# MC21R01_BoardtoBoard_connectors.net
KiCad netlist of a schematic drawn in Altium Designer
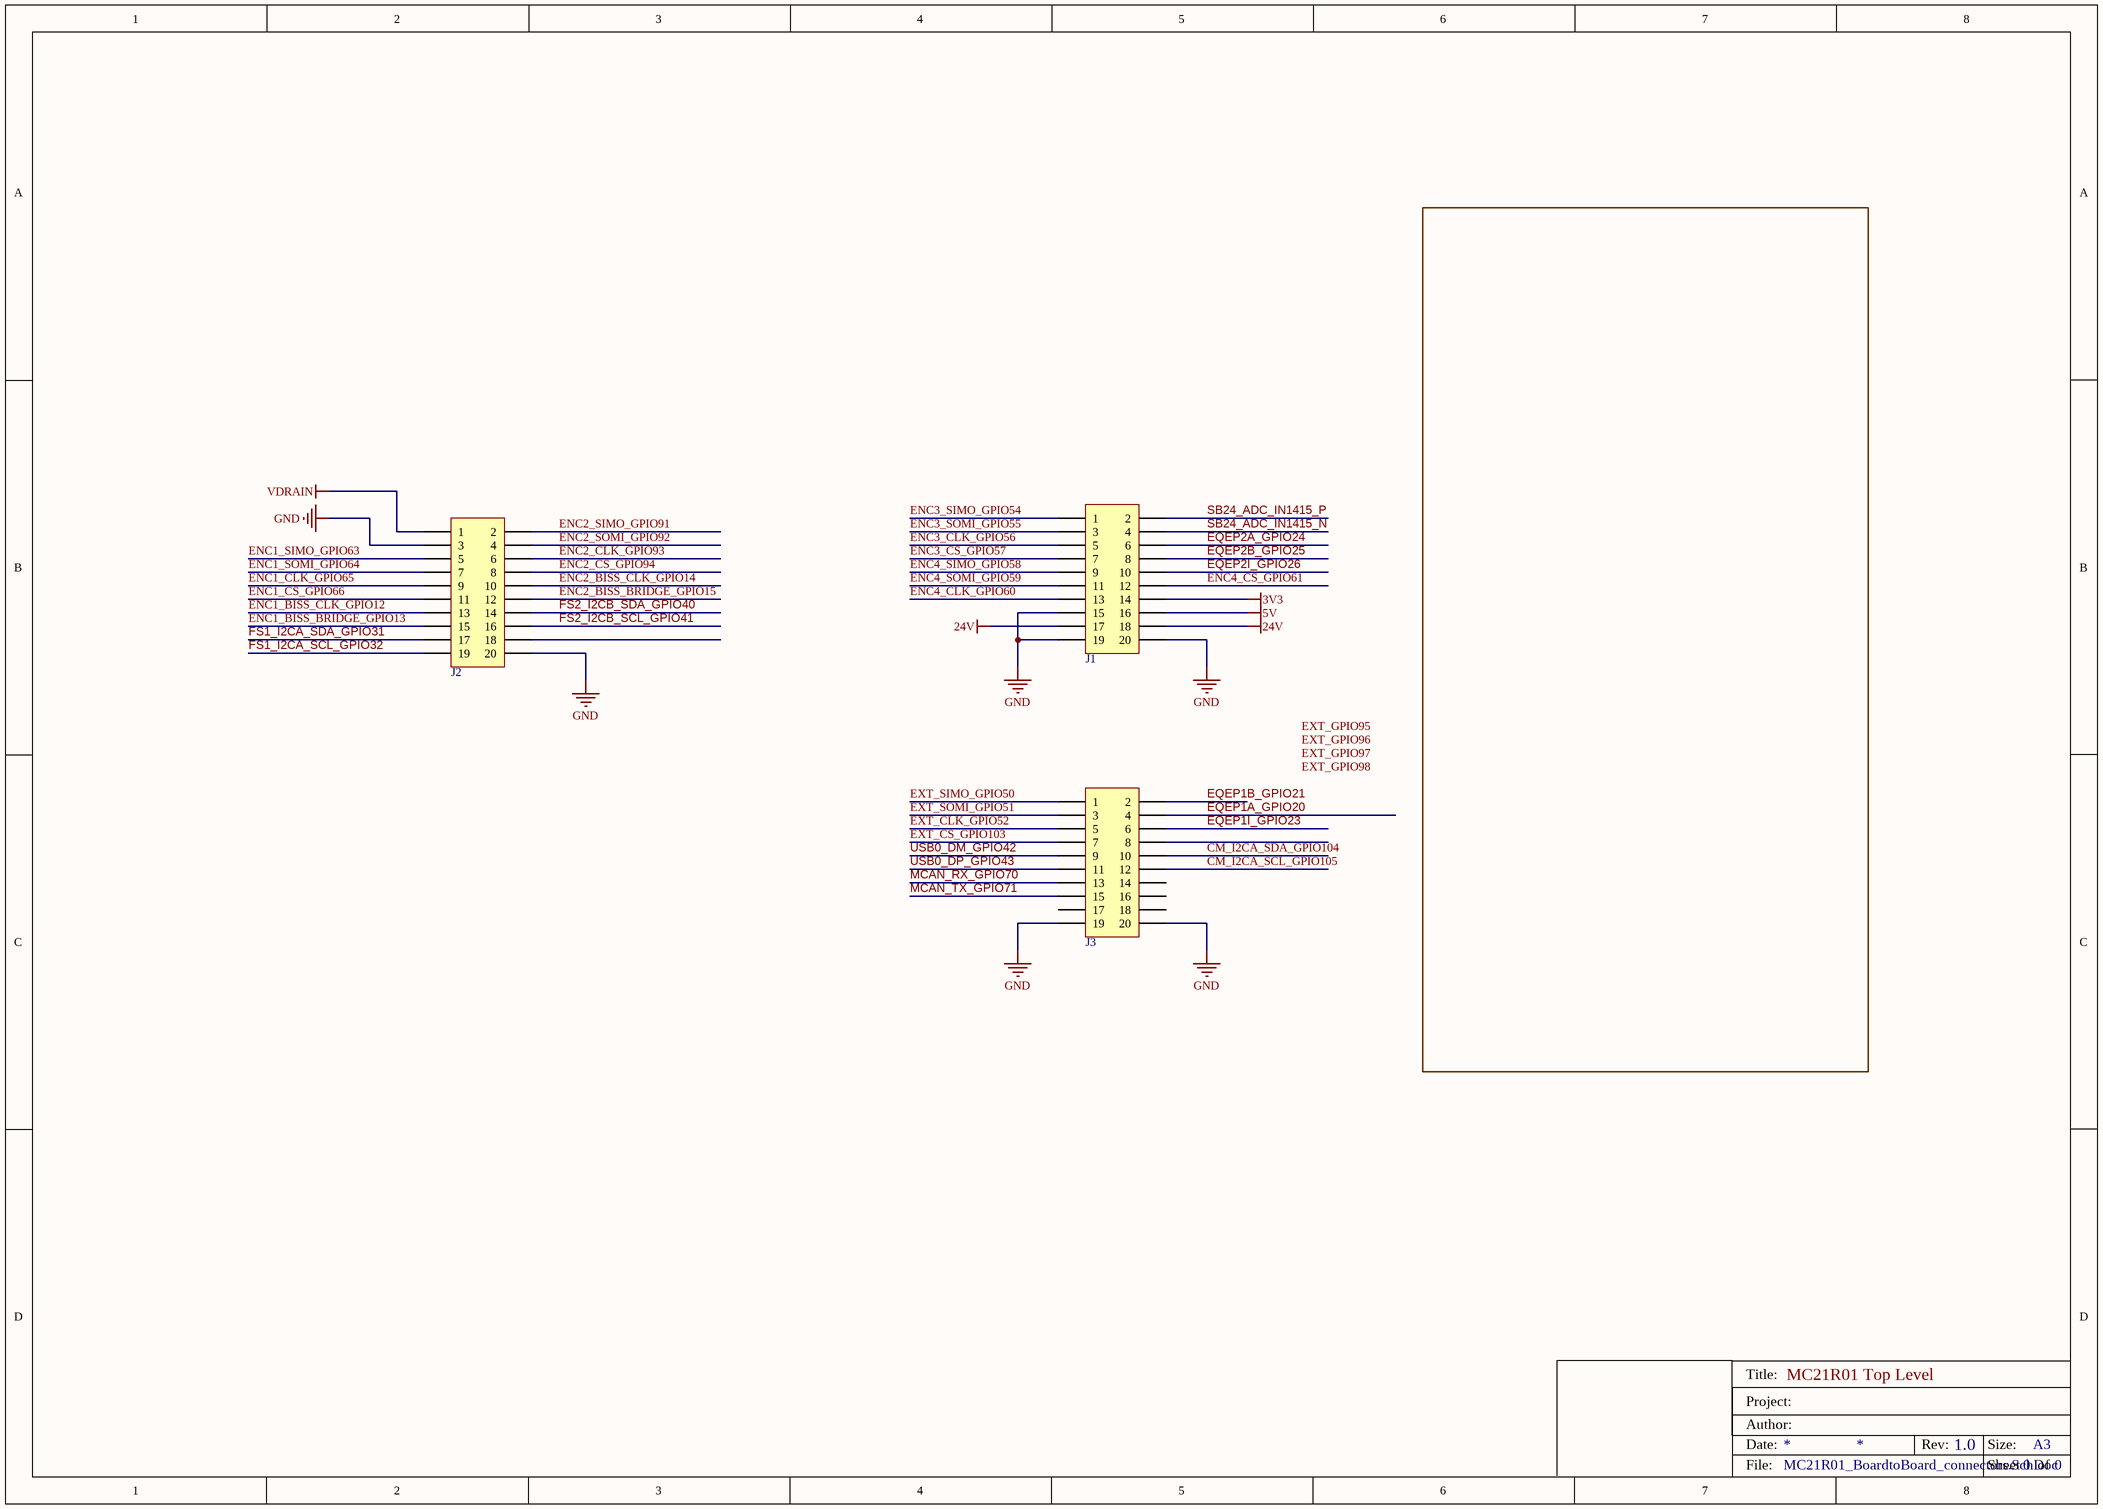
[diagram p0: MC21R01_BoardtoBoard_connectors.SchDoc]

(export (version "E")
  (design (tool "Eeschema 10.0.6"))
  (components
    (comp (ref "J1")
      (value "Amphenol 20021321-00020C4LF")
      (footprint "PAL_connectors:Amphenol 20021321-10020C4LF")
      (fields
        (field (name "MANUFACTURER") "Amphenol")
        (field (name "MANUFACTURER PART NUMBER") "20021321-00020C4LF")
      )
      (libsource (lib "PAL_connectors") (part "Amphenol 20021321-00020C4LF"))
    )
    (comp (ref "J2")
      (value "Amphenol 20021321-00020C4LF")
      (footprint "PAL_connectors:Amphenol 20021321-10020C4LF")
      (fields
        (field (name "MANUFACTURER") "Amphenol")
        (field (name "MANUFACTURER PART NUMBER") "20021321-00020C4LF")
      )
      (libsource (lib "PAL_connectors") (part "Amphenol 20021321-00020C4LF"))
    )
    (comp (ref "J3")
      (value "Amphenol 20021321-00020C4LF")
      (footprint "PAL_connectors:Amphenol 20021321-10020C4LF")
      (fields
        (field (name "MANUFACTURER") "Amphenol")
        (field (name "MANUFACTURER PART NUMBER") "20021321-00020C4LF")
      )
      (libsource (lib "PAL_connectors") (part "Amphenol 20021321-00020C4LF"))
    )
  )
  (nets
    (net (code "1") (name "/CM_I2CA_SCL_GPIO105") (class "Default")
      (node (ref "J3") (pin "12") (pinfunction "12_12") (pintype "passive"))
    )
    (net (code "2") (name "/CM_I2CA_SDA_GPIO104") (class "Default")
      (node (ref "J3") (pin "10") (pinfunction "10_10") (pintype "passive"))
    )
    (net (code "3") (name "/ENC1_BISS_BRIDGE_GPIO13") (class "Default")
      (node (ref "J2") (pin "15") (pinfunction "15_15") (pintype "passive"))
    )
    (net (code "4") (name "/ENC1_BISS_CLK_GPIO12") (class "Default")
      (node (ref "J2") (pin "13") (pinfunction "13_13") (pintype "passive"))
    )
    (net (code "5") (name "/ENC1_CLK_GPIO65") (class "Default")
      (node (ref "J2") (pin "9") (pinfunction "9_9") (pintype "passive"))
    )
    (net (code "6") (name "/ENC1_CS_GPIO66") (class "Default")
      (node (ref "J2") (pin "11") (pinfunction "11_11") (pintype "passive"))
    )
    (net (code "7") (name "/ENC1_SIMO_GPIO63") (class "Default")
      (node (ref "J2") (pin "5") (pinfunction "5_5") (pintype "passive"))
    )
    (net (code "8") (name "/ENC1_SOMI_GPIO64") (class "Default")
      (node (ref "J2") (pin "7") (pinfunction "7_7") (pintype "passive"))
    )
    (net (code "9") (name "/ENC2_BISS_BRIDGE_GPIO15") (class "Default")
      (node (ref "J2") (pin "12") (pinfunction "12_12") (pintype "passive"))
    )
    (net (code "10") (name "/ENC2_BISS_CLK_GPIO14") (class "Default")
      (node (ref "J2") (pin "10") (pinfunction "10_10") (pintype "passive"))
    )
    (net (code "11") (name "/ENC2_CLK_GPIO93") (class "Default")
      (node (ref "J2") (pin "6") (pinfunction "6_6") (pintype "passive"))
    )
    (net (code "12") (name "/ENC2_CS_GPIO94") (class "Default")
      (node (ref "J2") (pin "8") (pinfunction "8_8") (pintype "passive"))
    )
    (net (code "13") (name "/ENC2_SIMO_GPIO91") (class "Default")
      (node (ref "J2") (pin "2") (pinfunction "2_2") (pintype "passive"))
    )
    (net (code "14") (name "/ENC2_SOMI_GPIO92") (class "Default")
      (node (ref "J2") (pin "4") (pinfunction "4_4") (pintype "passive"))
    )
    (net (code "15") (name "/ENC3_CLK_GPIO56") (class "Default")
      (node (ref "J1") (pin "5") (pinfunction "5_5") (pintype "passive"))
    )
    (net (code "16") (name "/ENC3_CS_GPIO57") (class "Default")
      (node (ref "J1") (pin "7") (pinfunction "7_7") (pintype "passive"))
    )
    (net (code "17") (name "/ENC3_SIMO_GPIO54") (class "Default")
      (node (ref "J1") (pin "1") (pinfunction "1_1") (pintype "passive"))
    )
    (net (code "18") (name "/ENC3_SOMI_GPIO55") (class "Default")
      (node (ref "J1") (pin "3") (pinfunction "3_3") (pintype "passive"))
    )
    (net (code "19") (name "/ENC4_CLK_GPIO60") (class "Default")
      (node (ref "J1") (pin "13") (pinfunction "13_13") (pintype "passive"))
    )
    (net (code "20") (name "/ENC4_CS_GPIO61") (class "Default")
      (node (ref "J1") (pin "12") (pinfunction "12_12") (pintype "passive"))
    )
    (net (code "21") (name "/ENC4_SIMO_GPIO58") (class "Default")
      (node (ref "J1") (pin "9") (pinfunction "9_9") (pintype "passive"))
    )
    (net (code "22") (name "/ENC4_SOMI_GPIO59") (class "Default")
      (node (ref "J1") (pin "11") (pinfunction "11_11") (pintype "passive"))
    )
    (net (code "23") (name "/EQEP1A_GPIO20") (class "Default")
      (node (ref "J3") (pin "4") (pinfunction "4_4") (pintype "passive"))
    )
    (net (code "24") (name "/EQEP1B_GPIO21") (class "Default")
      (node (ref "J3") (pin "2") (pinfunction "2_2") (pintype "passive"))
    )
    (net (code "25") (name "/EQEP1I_GPIO23") (class "Default")
      (node (ref "J3") (pin "6") (pinfunction "6_6") (pintype "passive"))
    )
    (net (code "26") (name "/EQEP2A_GPIO24") (class "Default")
      (node (ref "J1") (pin "6") (pinfunction "6_6") (pintype "passive"))
    )
    (net (code "27") (name "/EQEP2B_GPIO25") (class "Default")
      (node (ref "J1") (pin "8") (pinfunction "8_8") (pintype "passive"))
    )
    (net (code "28") (name "/EQEP2I_GPIO26") (class "Default")
      (node (ref "J1") (pin "10") (pinfunction "10_10") (pintype "passive"))
    )
    (net (code "29") (name "/EXT_CLK_GPIO52") (class "Default")
      (node (ref "J3") (pin "5") (pinfunction "5_5") (pintype "passive"))
    )
    (net (code "30") (name "/EXT_CS_GPIO103") (class "Default")
      (node (ref "J3") (pin "7") (pinfunction "7_7") (pintype "passive"))
    )
    (net (code "35") (name "/EXT_SIMO_GPIO50") (class "Default")
      (node (ref "J3") (pin "1") (pinfunction "1_1") (pintype "passive"))
    )
    (net (code "36") (name "/EXT_SOMI_GPIO51") (class "Default")
      (node (ref "J3") (pin "3") (pinfunction "3_3") (pintype "passive"))
    )
    (net (code "37") (name "/FS1_I2CA_SCL_GPIO32") (class "Default")
      (node (ref "J2") (pin "19") (pinfunction "19_19") (pintype "passive"))
    )
    (net (code "38") (name "/FS1_I2CA_SDA_GPIO31") (class "Default")
      (node (ref "J2") (pin "17") (pinfunction "17_17") (pintype "passive"))
    )
    (net (code "39") (name "/FS2_I2CB_SCL_GPIO41") (class "Default")
      (node (ref "J2") (pin "16") (pinfunction "16_16") (pintype "passive"))
    )
    (net (code "40") (name "/FS2_I2CB_SDA_GPIO40") (class "Default")
      (node (ref "J2") (pin "14") (pinfunction "14_14") (pintype "passive"))
    )
    (net (code "41") (name "/MCAN_RX_GPIO70") (class "Default")
      (node (ref "J3") (pin "13") (pinfunction "13_13") (pintype "passive"))
    )
    (net (code "42") (name "/MCAN_TX_GPIO71") (class "Default")
      (node (ref "J3") (pin "15") (pinfunction "15_15") (pintype "passive"))
    )
    (net (code "43") (name "/SB24_ADC_IN1415_N") (class "Default")
      (node (ref "J1") (pin "4") (pinfunction "4_4") (pintype "passive"))
    )
    (net (code "44") (name "/SB24_ADC_IN1415_P") (class "Default")
      (node (ref "J1") (pin "2") (pinfunction "2_2") (pintype "passive"))
    )
    (net (code "45") (name "/USB0_DM_GPIO42") (class "Default")
      (node (ref "J3") (pin "9") (pinfunction "9_9") (pintype "passive"))
    )
    (net (code "46") (name "/USB0_DP_GPIO43") (class "Default")
      (node (ref "J3") (pin "11") (pinfunction "11_11") (pintype "passive"))
    )
    (net (code "47") (name "3V3") (class "Default")
      (node (ref "J1") (pin "14") (pinfunction "14_14") (pintype "passive"))
    )
    (net (code "48") (name "5V") (class "Default")
      (node (ref "J1") (pin "16") (pinfunction "16_16") (pintype "passive"))
    )
    (net (code "49") (name "24V") (class "Default")
      (node (ref "J1") (pin "17") (pinfunction "17_17") (pintype "passive"))
      (node (ref "J1") (pin "18") (pinfunction "18_18") (pintype "passive"))
    )
    (net (code "50") (name "GND") (class "Default")
      (node (ref "J1") (pin "15") (pinfunction "15_15") (pintype "passive"))
      (node (ref "J1") (pin "19") (pinfunction "19_19") (pintype "passive"))
      (node (ref "J1") (pin "20") (pinfunction "20_20") (pintype "passive"))
      (node (ref "J2") (pin "20") (pinfunction "20_20") (pintype "passive"))
      (node (ref "J2") (pin "3") (pinfunction "3_3") (pintype "passive"))
      (node (ref "J3") (pin "19") (pinfunction "19_19") (pintype "passive"))
      (node (ref "J3") (pin "20") (pinfunction "20_20") (pintype "passive"))
    )
    (net (code "51") (name "VDRAIN") (class "Default")
      (node (ref "J2") (pin "1") (pinfunction "1_1") (pintype "passive"))
    )
    (net (code "52") (name "unconnected-(J2-Pad18)") (class "Default")
      (node (ref "J2") (pin "18") (pinfunction "18_18") (pintype "passive"))
    )
    (net (code "53") (name "unconnected-(J3-Pad8)") (class "Default")
      (node (ref "J3") (pin "8") (pinfunction "8_8") (pintype "passive"))
    )
    (net (code "54") (name "unconnected-(J3-Pad14)") (class "Default")
      (node (ref "J3") (pin "14") (pinfunction "14_14") (pintype "passive"))
    )
    (net (code "55") (name "unconnected-(J3-Pad16)") (class "Default")
      (node (ref "J3") (pin "16") (pinfunction "16_16") (pintype "passive"))
    )
    (net (code "56") (name "unconnected-(J3-Pad17)") (class "Default")
      (node (ref "J3") (pin "17") (pinfunction "17_17") (pintype "passive"))
    )
    (net (code "57") (name "unconnected-(J3-Pad18)") (class "Default")
      (node (ref "J3") (pin "18") (pinfunction "18_18") (pintype "passive"))
    )
  )
)
